# VehicleBattVMonIoT_SMD.net
KiCad netlist of a schematic drawn in EAGLE
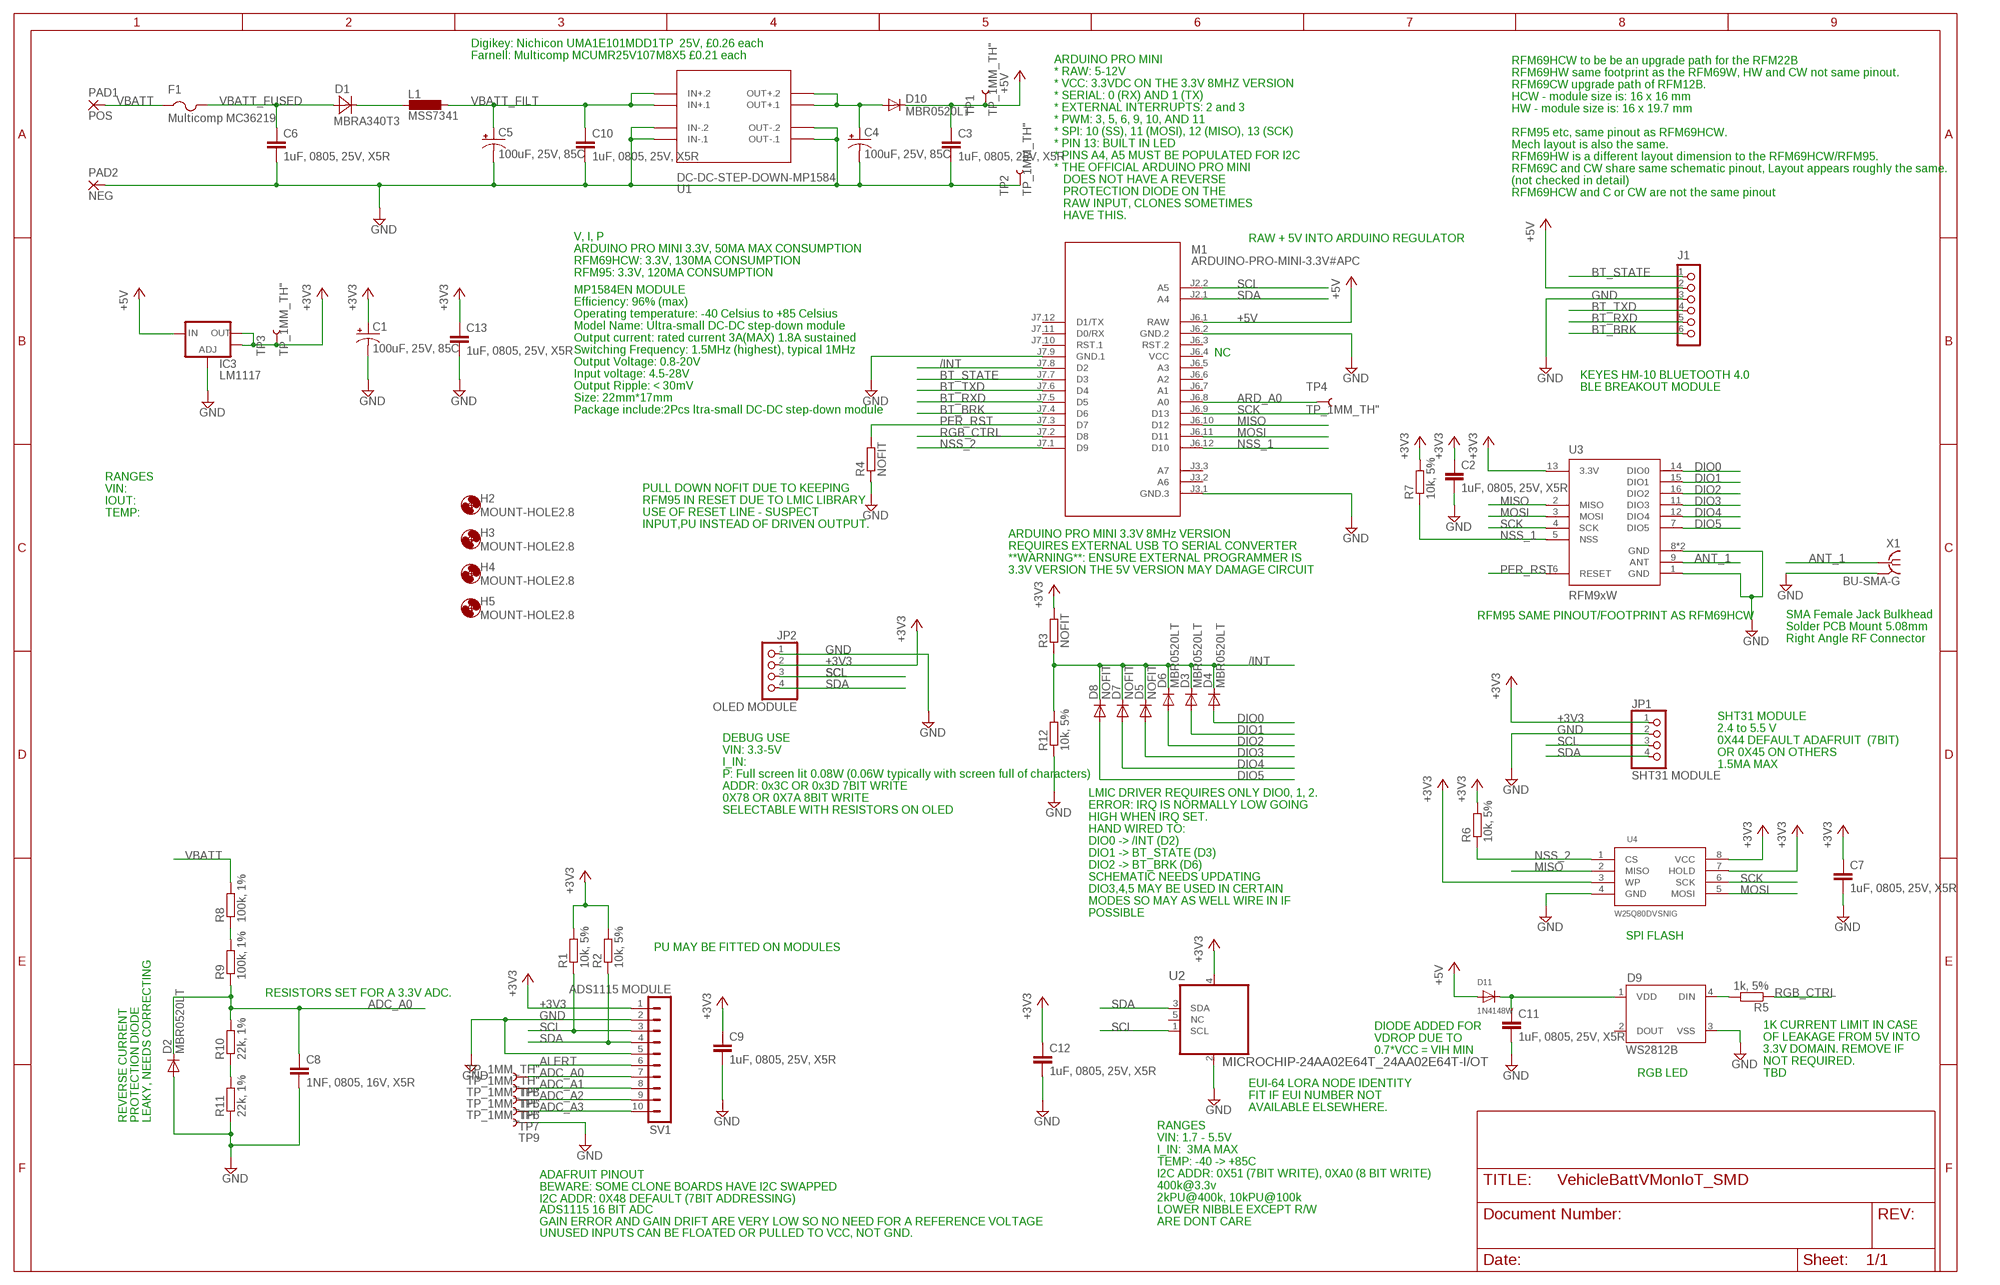
[diagram p0: schematic, sheet 1]

(export (version "E")
  (design (tool "Eeschema 10.0.6"))
  (components
    (comp (ref "C1")
      (value "100uF, 25V, 85C")
      (footprint "eagle-import:CPOL-RADIAL-100UF-25V")
      (fields (field (name "MF") "MULTICOMP") (field (name "MPN") "MCUMR25V107M8X5"))
      (libsource (lib "eagle-import") (part "CAP_POLPTH1"))
    )
    (comp (ref "C2")
      (value "1uF, 0805, 25V, X5R")
      (footprint "eagle-import:C0805")
      (fields (field (name "MF") "MULTICOMP") (field (name "MPN") "MC0805X105K250CT"))
      (libsource (lib "eagle-import") (part "C-EUC0805"))
    )
    (comp (ref "C3")
      (value "1uF, 0805, 25V, X5R")
      (footprint "eagle-import:C0805")
      (fields (field (name "MF") "MULTICOMP") (field (name "MPN") "MC0805X105K250CT"))
      (libsource (lib "eagle-import") (part "C-EUC0805"))
    )
    (comp (ref "C4")
      (value "100uF, 25V, 85C")
      (footprint "eagle-import:CPOL-RADIAL-100UF-25V")
      (fields (field (name "MF") "MULTICOMP") (field (name "MPN") "MCUMR25V107M8X5"))
      (libsource (lib "eagle-import") (part "CAP_POLPTH1"))
    )
    (comp (ref "C5")
      (value "100uF, 25V, 85C")
      (footprint "eagle-import:CPOL-RADIAL-100UF-25V")
      (fields (field (name "MF") "MULTICOMP") (field (name "MPN") "MCUMR25V107M8X5"))
      (libsource (lib "eagle-import") (part "CAP_POLPTH1"))
    )
    (comp (ref "C6")
      (value "1uF, 0805, 25V, X5R")
      (footprint "eagle-import:C0805")
      (fields (field (name "MF") "MULTICOMP") (field (name "MPN") "MC0805X105K250CT"))
      (libsource (lib "eagle-import") (part "C-EUC0805"))
    )
    (comp (ref "C7")
      (value "1uF, 0805, 25V, X5R")
      (footprint "eagle-import:C0805")
      (fields (field (name "MF") "MULTICOMP") (field (name "MPN") "MC0805X105K250CT"))
      (libsource (lib "eagle-import") (part "C-EUC0805"))
    )
    (comp (ref "C8")
      (value "1NF, 0805, 16V, X5R")
      (footprint "eagle-import:C0805")
      (fields (field (name "MF") "MULTICOMP") (field (name "MPN") "MCSH21B102K160CT"))
      (libsource (lib "eagle-import") (part "C-EUC0805"))
    )
    (comp (ref "C9")
      (value "1uF, 0805, 25V, X5R")
      (footprint "eagle-import:C0805")
      (fields (field (name "MF") "MULTICOMP") (field (name "MPN") "MC0805X105K250CT"))
      (libsource (lib "eagle-import") (part "C-EUC0805"))
    )
    (comp (ref "C10")
      (value "1uF, 0805, 25V, X5R")
      (footprint "eagle-import:C0805")
      (fields (field (name "MF") "MULTICOMP") (field (name "MPN") "MC0805X105K250CT"))
      (libsource (lib "eagle-import") (part "C-EUC0805"))
    )
    (comp (ref "C11")
      (value "1uF, 0805, 25V, X5R")
      (footprint "eagle-import:C0805")
      (fields (field (name "MF") "MULTICOMP") (field (name "MPN") "MC0805X105K250CT"))
      (libsource (lib "eagle-import") (part "C-EUC0805"))
    )
    (comp (ref "C12")
      (value "1uF, 0805, 25V, X5R")
      (footprint "eagle-import:C0805")
      (fields (field (name "MF") "MULTICOMP") (field (name "MPN") "MC0805X105K250CT"))
      (libsource (lib "eagle-import") (part "C-EUC0805"))
    )
    (comp (ref "C13")
      (value "1uF, 0805, 25V, X5R")
      (footprint "eagle-import:C0805")
      (fields (field (name "MF") "MULTICOMP") (field (name "MPN") "MC0805X105K250CT"))
      (libsource (lib "eagle-import") (part "C-EUC0805"))
    )
    (comp (ref "D1")
      (value "MBRA340T3")
      (footprint "eagle-import:SMA")
      (fields (field (name "MF") "ON SEMICONDUCTOR") (field (name "MPN") "MBRA340T3G"))
      (libsource (lib "eagle-import") (part "MBRA340T3"))
    )
    (comp (ref "D2")
      (value "MBR0520LT")
      (footprint "eagle-import:SOD123")
      (fields (field (name "MF") "DIODES INC.") (field (name "MPN") "B0520LW-7-F"))
      (libsource (lib "eagle-import") (part "MBR0520LT"))
    )
    (comp (ref "D3")
      (value "MBR0520LT")
      (footprint "eagle-import:SOD123")
      (fields (field (name "MF") "DIODES INC.") (field (name "MPN") "B0520LW-7-F"))
      (libsource (lib "eagle-import") (part "MBR0520LT"))
    )
    (comp (ref "D4")
      (value "MBR0520LT")
      (footprint "eagle-import:SOD123")
      (fields (field (name "MF") "DIODES INC.") (field (name "MPN") "B0520LW-7-F"))
      (libsource (lib "eagle-import") (part "MBR0520LT"))
    )
    (comp (ref "D5")
      (value "NOFIT")
      (footprint "eagle-import:SOD123")
      (fields (field (name "MF") "DIODES INC.") (field (name "MPN") "B0520LW-7-F"))
      (libsource (lib "eagle-import") (part "MBR0520LT"))
    )
    (comp (ref "D6")
      (value "MBR0520LT")
      (footprint "eagle-import:SOD123")
      (fields (field (name "MF") "DIODES INC.") (field (name "MPN") "B0520LW-7-F"))
      (libsource (lib "eagle-import") (part "MBR0520LT"))
    )
    (comp (ref "D7")
      (value "NOFIT")
      (footprint "eagle-import:SOD123")
      (fields (field (name "MF") "DIODES INC.") (field (name "MPN") "B0520LW-7-F"))
      (libsource (lib "eagle-import") (part "MBR0520LT"))
    )
    (comp (ref "D8")
      (value "NOFIT")
      (footprint "eagle-import:SOD123")
      (fields (field (name "MF") "DIODES INC.") (field (name "MPN") "B0520LW-7-F"))
      (libsource (lib "eagle-import") (part "MBR0520LT"))
    )
    (comp (ref "D9")
      (value "WS2812B")
      (footprint "eagle-import:WS2812B")
      (libsource (lib "eagle-import") (part "WS2812B"))
    )
    (comp (ref "D10")
      (value "MBR0520LT")
      (footprint "eagle-import:SOD123")
      (fields (field (name "MF") "DIODES INC.") (field (name "MPN") "B0520LW-7-F"))
      (libsource (lib "eagle-import") (part "MBR0520LT"))
    )
    (comp (ref "D11")
      (value "1N4148W")
      (footprint "eagle-import:SOD-323F")
      (fields (field (name "MF") "MULTICOMP") (field (name "MPN") "1N4148WS."))
      (libsource (lib "eagle-import") (part "DIODESOD-323F"))
    )
    (comp (ref "F1")
      (value "Multicomp MC36219")
      (footprint "eagle-import:1812")
      (fields (field (name "MF") "MULTICOMP") (field (name "MPN") "MC36219."))
      (libsource (lib "eagle-import") (part "PTCFUSE-1812"))
    )
    (comp (ref "H2")
      (value "MOUNT-HOLE2.8")
      (footprint "eagle-import:2,8")
      (libsource (lib "eagle-import") (part "MOUNT-HOLE2.8"))
    )
    (comp (ref "H3")
      (value "MOUNT-HOLE2.8")
      (footprint "eagle-import:2,8")
      (libsource (lib "eagle-import") (part "MOUNT-HOLE2.8"))
    )
    (comp (ref "H4")
      (value "MOUNT-HOLE2.8")
      (footprint "eagle-import:2,8")
      (libsource (lib "eagle-import") (part "MOUNT-HOLE2.8"))
    )
    (comp (ref "H5")
      (value "MOUNT-HOLE2.8")
      (footprint "eagle-import:2,8")
      (libsource (lib "eagle-import") (part "MOUNT-HOLE2.8"))
    )
    (comp (ref "IC3")
      (value "LM1117")
      (footprint "eagle-import:SOT223")
      (fields (field (name "MF") "STMICROELECTRONICS") (field (name "MPN") "LD1117S33TR"))
      (libsource (lib "eagle-import") (part "V_REG_LM1117SOT223"))
    )
    (comp (ref "J1")
      (value "HM-10 MODULE")
      (footprint "eagle-import:M1X6_MALE_RIGHT_ANGLED_SMD")
      (libsource (lib "eagle-import") (part "CON_HEADER_1X06-SMD-RIGHT-ANGLED"))
    )
    (comp (ref "JP1")
      (value "SHT31 MODULE")
      (footprint "eagle-import:1X04")
      (libsource (lib "eagle-import") (part "PINHD-1X4"))
    )
    (comp (ref "JP2")
      (value "OLED MODULE")
      (footprint "eagle-import:1X04")
      (libsource (lib "eagle-import") (part "PINHD-1X4"))
    )
    (comp (ref "L1")
      (value "MSS7341")
      (footprint "eagle-import:MSS7341")
      (fields (field (name "MF") "COILCRAFT") (field (name "MPN") "MSS7341-683MLD"))
      (libsource (lib "eagle-import") (part "MSS7341"))
    )
    (comp (ref "M1")
      (value "ARDUINO-PRO-MINI-3.3V#APC")
      (footprint "eagle-import:ARDUINO-PRO-MINI#APC")
      (libsource (lib "eagle-import") (part "ARDUINO-PRO-MINI-#APC3.3V"))
    )
    (comp (ref "PAD1")
      (value "POS")
      (footprint "eagle-import:3,81_1,4")
      (libsource (lib "eagle-import") (part "3,81/1,4"))
    )
    (comp (ref "PAD2")
      (value "NEG")
      (footprint "eagle-import:3,81_1,4")
      (libsource (lib "eagle-import") (part "3,81/1,4"))
    )
    (comp (ref "R1")
      (value "10k, 5%")
      (footprint "eagle-import:R0805")
      (fields (field (name "MF") "MULTICOMP") (field (name "MPN") "MC01W0805510K"))
      (libsource (lib "eagle-import") (part "R-EU_R0805"))
    )
    (comp (ref "R2")
      (value "10k, 5%")
      (footprint "eagle-import:R0805")
      (fields (field (name "MF") "MULTICOMP") (field (name "MPN") "MC01W0805510K"))
      (libsource (lib "eagle-import") (part "R-EU_R0805"))
    )
    (comp (ref "R3")
      (value "NOFIT")
      (footprint "eagle-import:R0805")
      (fields (field (name "MF") "MULTICOMP") (field (name "MPN") "MC01W0805510K"))
      (libsource (lib "eagle-import") (part "R-EU_R0805"))
    )
    (comp (ref "R4")
      (value "NOFIT")
      (footprint "eagle-import:R0805")
      (fields (field (name "MF") "MULTICOMP") (field (name "MPN") "MC01W0805510K"))
      (libsource (lib "eagle-import") (part "R-EU_R0805"))
    )
    (comp (ref "R5")
      (value "1k, 5%")
      (footprint "eagle-import:R0805")
      (fields (field (name "MF") "WELWYN") (field (name "MPN") "WCR0805-1K0FI"))
      (libsource (lib "eagle-import") (part "R-EU_R0805"))
    )
    (comp (ref "R6")
      (value "10k, 5%")
      (footprint "eagle-import:R0805")
      (fields (field (name "MF") "MULTICOMP") (field (name "MPN") "MC01W0805510K"))
      (libsource (lib "eagle-import") (part "R-EU_R0805"))
    )
    (comp (ref "R7")
      (value "10k, 5%")
      (footprint "eagle-import:R0805")
      (fields (field (name "MF") "MULTICOMP") (field (name "MPN") "MC01W0805510K"))
      (libsource (lib "eagle-import") (part "R-EU_R0805"))
    )
    (comp (ref "R8")
      (value "100k, 1%")
      (footprint "eagle-import:R0805")
      (fields (field (name "MF") "YAGEO (PHYCOMP)") (field (name "MPN") "RC0805FR-07100KL"))
      (libsource (lib "eagle-import") (part "R-EU_R0805"))
    )
    (comp (ref "R9")
      (value "100k, 1%")
      (footprint "eagle-import:R0805")
      (fields (field (name "MF") "YAGEO (PHYCOMP)") (field (name "MPN") "RC0805FR-07100KL"))
      (libsource (lib "eagle-import") (part "R-EU_R0805"))
    )
    (comp (ref "R10")
      (value "22k, 1%")
      (footprint "eagle-import:R0805")
      (fields (field (name "MF") "WELWYN") (field (name "MPN") "WCR0805-22KFI"))
      (libsource (lib "eagle-import") (part "R-EU_R0805"))
    )
    (comp (ref "R11")
      (value "22k, 1%")
      (footprint "eagle-import:R0805")
      (fields (field (name "MF") "WELWYN") (field (name "MPN") "WCR0805-22KFI"))
      (libsource (lib "eagle-import") (part "R-EU_R0805"))
    )
    (comp (ref "R12")
      (value "10k, 5%")
      (footprint "eagle-import:R0805")
      (fields (field (name "MF") "MULTICOMP") (field (name "MPN") "MC01W0805510K"))
      (libsource (lib "eagle-import") (part "R-EU_R0805"))
    )
    (comp (ref "SV1")
      (value "ADS1115 MODULE")
      (footprint "eagle-import:MA10-1W")
      (libsource (lib "eagle-import") (part "MA10-1W"))
    )
    (comp (ref "TP1")
      (value "TP_1MM_TH\"")
      (footprint "eagle-import:TP_1MM_TH")
      (libsource (lib "eagle-import") (part "TP_1MM_TH{dblquote}"))
    )
    (comp (ref "TP2")
      (value "TP_1MM_TH\"")
      (footprint "eagle-import:TP_1MM_TH")
      (libsource (lib "eagle-import") (part "TP_1MM_TH{dblquote}"))
    )
    (comp (ref "TP3")
      (value "TP_1MM_TH\"")
      (footprint "eagle-import:TP_1MM_TH")
      (libsource (lib "eagle-import") (part "TP_1MM_TH{dblquote}"))
    )
    (comp (ref "TP4")
      (value "TP_1MM_TH\"")
      (footprint "eagle-import:TP_1MM_TH")
      (libsource (lib "eagle-import") (part "TP_1MM_TH{dblquote}"))
    )
    (comp (ref "TP5")
      (value "TP_1MM_TH\"")
      (footprint "eagle-import:TP_1MM_TH")
      (libsource (lib "eagle-import") (part "TP_1MM_TH{dblquote}"))
    )
    (comp (ref "TP6")
      (value "TP_1MM_TH\"")
      (footprint "eagle-import:TP_1MM_TH")
      (libsource (lib "eagle-import") (part "TP_1MM_TH{dblquote}"))
    )
    (comp (ref "TP7")
      (value "TP_1MM_TH\"")
      (footprint "eagle-import:TP_1MM_TH")
      (libsource (lib "eagle-import") (part "TP_1MM_TH{dblquote}"))
    )
    (comp (ref "TP8")
      (value "TP_1MM_TH\"")
      (footprint "eagle-import:TP_1MM_TH")
      (libsource (lib "eagle-import") (part "TP_1MM_TH{dblquote}"))
    )
    (comp (ref "TP9")
      (value "TP_1MM_TH\"")
      (footprint "eagle-import:TP_1MM_TH")
      (libsource (lib "eagle-import") (part "TP_1MM_TH{dblquote}"))
    )
    (comp (ref "U1")
      (value "DC-DC-STEP-DOWN-MP1584")
      (footprint "eagle-import:DC-DC-STEP-DOWN-MP1584")
      (libsource (lib "eagle-import") (part "DC-DC-STEP-DOWN-MP1584"))
    )
    (comp (ref "U2")
      (value "MICROCHIP-24AA02E64T_24AA02E64T-I/OT")
      (footprint "eagle-import:MICROCHIP-24AA02E64T_SOT95P270X145-5N")
      (fields (field (name "MPN") "24AA02E64T-I/OT"))
      (libsource (lib "eagle-import") (part "MICROCHIP-24AA02E64T_24AA02E64T-I/OT"))
    )
    (comp (ref "U3")
      (value "RFM9xW")
      (footprint "eagle-import:RFM69HCW-XXXS2")
      (libsource (lib "eagle-import") (part "RFM69HCW"))
    )
    (comp (ref "U4")
      (value "W25Q80DVSNIG")
      (footprint "eagle-import:SO08")
      (libsource (lib "eagle-import") (part "SPI_FLASH-X25XXSMD"))
    )
    (comp (ref "X1")
      (value "BU-SMA-G")
      (footprint "eagle-import:BU-SMA-G")
      (fields
        (field (name "MF") "AMP - TE CONNECTIVITY")
        (field (name "MPN") "5-1814400-1")
        (field (name "OC_FARNELL") "1248989")
      )
      (libsource (lib "eagle-import") (part "BU-SMA-G"))
    )
  )
  (nets
    (net (code "1") (name "+3V3") (class "Default")
      (node (ref "C1") (pin "1") (pinfunction "+_1") (pintype "passive"))
      (node (ref "C12") (pin "1") (pinfunction "1_1") (pintype "passive"))
      (node (ref "C13") (pin "1") (pinfunction "1_1") (pintype "passive"))
      (node (ref "C2") (pin "1") (pinfunction "1_1") (pintype "passive"))
      (node (ref "C7") (pin "1") (pinfunction "1_1") (pintype "passive"))
      (node (ref "C9") (pin "1") (pinfunction "1_1") (pintype "passive"))
      (node (ref "IC3") (pin "2") (pinfunction "OUT_2") (pintype "output"))
      (node (ref "IC3") (pin "4") (pinfunction "OUT_4") (pintype "output"))
      (node (ref "JP1") (pin "1") (pinfunction "1_1") (pintype "passive"))
      (node (ref "JP2") (pin "2") (pinfunction "2_2") (pintype "passive"))
      (node (ref "R1") (pin "2") (pinfunction "2_2") (pintype "passive"))
      (node (ref "R2") (pin "2") (pinfunction "2_2") (pintype "passive"))
      (node (ref "R3") (pin "2") (pinfunction "2_2") (pintype "passive"))
      (node (ref "R6") (pin "2") (pinfunction "2_2") (pintype "passive"))
      (node (ref "R7") (pin "2") (pinfunction "2_2") (pintype "passive"))
      (node (ref "SV1") (pin "1") (pinfunction "1_1") (pintype "passive"))
      (node (ref "TP3") (pin "P$1") (pinfunction "1_P$1") (pintype "bidirectional"))
      (node (ref "U2") (pin "4") (pinfunction "VCC_4") (pintype "power_in"))
      (node (ref "U3") (pin "13") (pinfunction "3.3V_13") (pintype "power_in"))
      (node (ref "U4") (pin "3") (pinfunction "WP_3") (pintype "bidirectional"))
      (node (ref "U4") (pin "7") (pinfunction "HOLD_7") (pintype "bidirectional"))
      (node (ref "U4") (pin "8") (pinfunction "VCC_8") (pintype "bidirectional"))
    )
    (net (code "2") (name "+5V") (class "Default")
      (node (ref "C3") (pin "1") (pinfunction "1_1") (pintype "passive"))
      (node (ref "D10") (pin "C") (pinfunction "C_C") (pintype "passive"))
      (node (ref "D11") (pin "A") (pinfunction "A_A") (pintype "passive"))
      (node (ref "IC3") (pin "3") (pinfunction "IN_3") (pintype "input"))
      (node (ref "J1") (pin "2") (pinfunction "2_2") (pintype "bidirectional"))
      (node (ref "M1") (pin "J6.1") (pinfunction "RAW_J6.1") (pintype "power_in"))
      (node (ref "TP1") (pin "P$1") (pinfunction "1_P$1") (pintype "bidirectional"))
    )
    (net (code "3") (name "/ADC_A0") (class "Default")
      (node (ref "C8") (pin "1") (pinfunction "1_1") (pintype "passive"))
      (node (ref "D2") (pin "C") (pinfunction "C_C") (pintype "passive"))
      (node (ref "R10") (pin "2") (pinfunction "2_2") (pintype "passive"))
      (node (ref "R9") (pin "1") (pinfunction "1_1") (pintype "passive"))
      (node (ref "SV1") (pin "7") (pinfunction "7_7") (pintype "passive"))
      (node (ref "TP8") (pin "P$1") (pinfunction "1_P$1") (pintype "bidirectional"))
    )
    (net (code "4") (name "/ADC_A1") (class "Default")
      (node (ref "SV1") (pin "8") (pinfunction "8_8") (pintype "passive"))
      (node (ref "TP5") (pin "P$1") (pinfunction "1_P$1") (pintype "bidirectional"))
    )
    (net (code "5") (name "/ADC_A2") (class "Default")
      (node (ref "SV1") (pin "9") (pinfunction "9_9") (pintype "passive"))
      (node (ref "TP6") (pin "P$1") (pinfunction "1_P$1") (pintype "bidirectional"))
    )
    (net (code "6") (name "/ADC_A3") (class "Default")
      (node (ref "SV1") (pin "10") (pinfunction "10_10") (pintype "passive"))
      (node (ref "TP7") (pin "P$1") (pinfunction "1_P$1") (pintype "bidirectional"))
    )
    (net (code "7") (name "/ALERT") (class "Default")
      (node (ref "SV1") (pin "6") (pinfunction "6_6") (pintype "passive"))
    )
    (net (code "8") (name "/ANT_1") (class "Default")
      (node (ref "U3") (pin "9") (pinfunction "ANT_9") (pintype "passive"))
      (node (ref "X1") (pin "1") (pinfunction "1_1") (pintype "passive"))
    )
    (net (code "9") (name "/ARD_A0") (class "Default")
      (node (ref "M1") (pin "J6.8") (pinfunction "A0_J6.8") (pintype "bidirectional"))
      (node (ref "TP4") (pin "P$1") (pinfunction "1_P$1") (pintype "bidirectional"))
    )
    (net (code "10") (name "/BT_BRK") (class "Default")
      (node (ref "J1") (pin "6") (pinfunction "6_6") (pintype "passive"))
      (node (ref "M1") (pin "J7.4") (pinfunction "D6_J7.4") (pintype "bidirectional"))
    )
    (net (code "11") (name "/BT_RXD") (class "Default")
      (node (ref "J1") (pin "5") (pinfunction "5_5") (pintype "passive"))
      (node (ref "M1") (pin "J7.5") (pinfunction "D5_J7.5") (pintype "bidirectional"))
    )
    (net (code "12") (name "/BT_STATE") (class "Default")
      (node (ref "J1") (pin "1") (pinfunction "1_1") (pintype "bidirectional"))
      (node (ref "M1") (pin "J7.7") (pinfunction "D3_J7.7") (pintype "bidirectional"))
    )
    (net (code "13") (name "/BT_TXD") (class "Default")
      (node (ref "J1") (pin "4") (pinfunction "4_4") (pintype "passive"))
      (node (ref "M1") (pin "J7.6") (pinfunction "D4_J7.6") (pintype "bidirectional"))
    )
    (net (code "14") (name "/DIO0") (class "Default")
      (node (ref "D4") (pin "A") (pinfunction "A_A") (pintype "passive"))
      (node (ref "U3") (pin "14") (pinfunction "DIO0_14") (pintype "bidirectional"))
    )
    (net (code "15") (name "/DIO1") (class "Default")
      (node (ref "D3") (pin "A") (pinfunction "A_A") (pintype "passive"))
      (node (ref "U3") (pin "15") (pinfunction "DIO1_15") (pintype "bidirectional"))
    )
    (net (code "16") (name "/DIO2") (class "Default")
      (node (ref "D6") (pin "A") (pinfunction "A_A") (pintype "passive"))
      (node (ref "U3") (pin "16") (pinfunction "DIO2_16") (pintype "bidirectional"))
    )
    (net (code "17") (name "/DIO3") (class "Default")
      (node (ref "D5") (pin "A") (pinfunction "A_A") (pintype "passive"))
      (node (ref "U3") (pin "11") (pinfunction "DIO3_11") (pintype "bidirectional"))
    )
    (net (code "18") (name "/DIO4") (class "Default")
      (node (ref "D7") (pin "A") (pinfunction "A_A") (pintype "passive"))
      (node (ref "U3") (pin "12") (pinfunction "DIO4_12") (pintype "bidirectional"))
    )
    (net (code "19") (name "/DIO5") (class "Default")
      (node (ref "D8") (pin "A") (pinfunction "A_A") (pintype "passive"))
      (node (ref "U3") (pin "7") (pinfunction "DIO5_7") (pintype "bidirectional"))
    )
    (net (code "20") (name "/MISO") (class "Default")
      (node (ref "M1") (pin "J6.10") (pinfunction "D12_J6.10") (pintype "bidirectional"))
      (node (ref "U3") (pin "2") (pinfunction "MISO_2") (pintype "bidirectional"))
      (node (ref "U4") (pin "2") (pinfunction "MISO_2") (pintype "bidirectional"))
    )
    (net (code "21") (name "/MOSI") (class "Default")
      (node (ref "M1") (pin "J6.11") (pinfunction "D11_J6.11") (pintype "bidirectional"))
      (node (ref "U3") (pin "3") (pinfunction "MOSI_3") (pintype "input"))
      (node (ref "U4") (pin "5") (pinfunction "MOSI_5") (pintype "bidirectional"))
    )
    (net (code "22") (name "/NSS_1") (class "Default")
      (node (ref "M1") (pin "J6.12") (pinfunction "D10_J6.12") (pintype "bidirectional"))
      (node (ref "R7") (pin "1") (pinfunction "1_1") (pintype "passive"))
      (node (ref "U3") (pin "5") (pinfunction "NSS_5") (pintype "input"))
    )
    (net (code "23") (name "/NSS_2") (class "Default")
      (node (ref "M1") (pin "J7.1") (pinfunction "D9_J7.1") (pintype "bidirectional"))
      (node (ref "R6") (pin "1") (pinfunction "1_1") (pintype "passive"))
      (node (ref "U4") (pin "1") (pinfunction "CS_1") (pintype "bidirectional"))
    )
    (net (code "24") (name "/PER_RST") (class "Default")
      (node (ref "M1") (pin "J7.3") (pinfunction "D7_J7.3") (pintype "bidirectional"))
      (node (ref "R4") (pin "2") (pinfunction "2_2") (pintype "passive"))
      (node (ref "U3") (pin "6") (pinfunction "RESET_6") (pintype "input"))
    )
    (net (code "25") (name "/RGB_CTRL") (class "Default")
      (node (ref "M1") (pin "J7.2") (pinfunction "D8_J7.2") (pintype "bidirectional"))
      (node (ref "R5") (pin "1") (pinfunction "1_1") (pintype "passive"))
    )
    (net (code "26") (name "/SCK") (class "Default")
      (node (ref "M1") (pin "J6.9") (pinfunction "D13_J6.9") (pintype "bidirectional"))
      (node (ref "U3") (pin "4") (pinfunction "SCK_4") (pintype "input"))
      (node (ref "U4") (pin "6") (pinfunction "SCK_6") (pintype "bidirectional"))
    )
    (net (code "27") (name "/SCL") (class "Default")
      (node (ref "JP1") (pin "3") (pinfunction "3_3") (pintype "passive"))
      (node (ref "JP2") (pin "3") (pinfunction "3_3") (pintype "passive"))
      (node (ref "M1") (pin "J2.2") (pinfunction "A5_J2.2") (pintype "bidirectional"))
      (node (ref "R1") (pin "1") (pinfunction "1_1") (pintype "passive"))
      (node (ref "SV1") (pin "3") (pinfunction "3_3") (pintype "passive"))
      (node (ref "U2") (pin "1") (pinfunction "SCL_1") (pintype "input"))
    )
    (net (code "28") (name "/SDA") (class "Default")
      (node (ref "JP1") (pin "4") (pinfunction "4_4") (pintype "passive"))
      (node (ref "JP2") (pin "4") (pinfunction "4_4") (pintype "passive"))
      (node (ref "M1") (pin "J2.1") (pinfunction "A4_J2.1") (pintype "bidirectional"))
      (node (ref "R2") (pin "1") (pinfunction "1_1") (pintype "passive"))
      (node (ref "SV1") (pin "4") (pinfunction "4_4") (pintype "passive"))
      (node (ref "U2") (pin "3") (pinfunction "SDA_3") (pintype "bidirectional"))
    )
    (net (code "29") (name "/VBATT") (class "Default")
      (node (ref "F1") (pin "1") (pinfunction "1_1") (pintype "passive"))
      (node (ref "PAD1") (pin "1") (pinfunction "P_1") (pintype "passive"))
      (node (ref "R8") (pin "2") (pinfunction "2_2") (pintype "passive"))
    )
    (net (code "30") (name "/VBATT_FILT") (class "Default")
      (node (ref "C10") (pin "1") (pinfunction "1_1") (pintype "passive"))
      (node (ref "C5") (pin "1") (pinfunction "+_1") (pintype "passive"))
      (node (ref "L1") (pin "2") (pinfunction "2_2") (pintype "passive"))
      (node (ref "U1") (pin "IN+.1") (pinfunction "IN+.1_IN+.1") (pintype "bidirectional"))
      (node (ref "U1") (pin "IN+.2") (pinfunction "IN+.2_IN+.2") (pintype "bidirectional"))
    )
    (net (code "31") (name "/VBATT_FUSED") (class "Default")
      (node (ref "C6") (pin "1") (pinfunction "1_1") (pintype "passive"))
      (node (ref "D1") (pin "A") (pinfunction "A_A") (pintype "passive"))
      (node (ref "F1") (pin "2") (pinfunction "2_2") (pintype "passive"))
    )
    (net (code "32") (name "/VCC") (class "Default")
      (node (ref "M1") (pin "J6.4") (pinfunction "VCC_J6.4") (pintype "power_in"))
    )
    (net (code "33") (name "/{slash}INT") (class "Default")
      (node (ref "D3") (pin "C") (pinfunction "C_C") (pintype "passive"))
      (node (ref "D4") (pin "C") (pinfunction "C_C") (pintype "passive"))
      (node (ref "D5") (pin "C") (pinfunction "C_C") (pintype "passive"))
      (node (ref "D6") (pin "C") (pinfunction "C_C") (pintype "passive"))
      (node (ref "D7") (pin "C") (pinfunction "C_C") (pintype "passive"))
      (node (ref "D8") (pin "C") (pinfunction "C_C") (pintype "passive"))
      (node (ref "M1") (pin "J7.8") (pinfunction "D2_J7.8") (pintype "bidirectional"))
      (node (ref "R12") (pin "2") (pinfunction "2_2") (pintype "passive"))
      (node (ref "R3") (pin "1") (pinfunction "1_1") (pintype "passive"))
    )
    (net (code "34") (name "GND") (class "Default")
      (node (ref "C1") (pin "2") (pinfunction "-_2") (pintype "passive"))
      (node (ref "C10") (pin "2") (pinfunction "2_2") (pintype "passive"))
      (node (ref "C11") (pin "2") (pinfunction "2_2") (pintype "passive"))
      (node (ref "C12") (pin "2") (pinfunction "2_2") (pintype "passive"))
      (node (ref "C13") (pin "2") (pinfunction "2_2") (pintype "passive"))
      (node (ref "C2") (pin "2") (pinfunction "2_2") (pintype "passive"))
      (node (ref "C3") (pin "2") (pinfunction "2_2") (pintype "passive"))
      (node (ref "C4") (pin "2") (pinfunction "-_2") (pintype "passive"))
      (node (ref "C5") (pin "2") (pinfunction "-_2") (pintype "passive"))
      (node (ref "C6") (pin "2") (pinfunction "2_2") (pintype "passive"))
      (node (ref "C7") (pin "2") (pinfunction "2_2") (pintype "passive"))
      (node (ref "C8") (pin "2") (pinfunction "2_2") (pintype "passive"))
      (node (ref "C9") (pin "2") (pinfunction "2_2") (pintype "passive"))
      (node (ref "D2") (pin "A") (pinfunction "A_A") (pintype "passive"))
      (node (ref "D9") (pin "3") (pinfunction "VSS_3") (pintype "power_in"))
      (node (ref "IC3") (pin "1") (pinfunction "ADJ_1") (pintype "input"))
      (node (ref "J1") (pin "3") (pinfunction "3_3") (pintype "passive"))
      (node (ref "JP1") (pin "2") (pinfunction "2_2") (pintype "passive"))
      (node (ref "JP2") (pin "1") (pinfunction "1_1") (pintype "passive"))
      (node (ref "M1") (pin "J3.1") (pinfunction "GND.3_J3.1") (pintype "bidirectional"))
      (node (ref "M1") (pin "J6.2") (pinfunction "GND.2_J6.2") (pintype "power_in"))
      (node (ref "M1") (pin "J7.9") (pinfunction "GND.1_J7.9") (pintype "power_in"))
      (node (ref "PAD2") (pin "1") (pinfunction "P_1") (pintype "passive"))
      (node (ref "R11") (pin "1") (pinfunction "1_1") (pintype "passive"))
      (node (ref "R12") (pin "1") (pinfunction "1_1") (pintype "passive"))
      (node (ref "R4") (pin "1") (pinfunction "1_1") (pintype "passive"))
      (node (ref "SV1") (pin "2") (pinfunction "2_2") (pintype "passive"))
      (node (ref "SV1") (pin "5") (pinfunction "5_5") (pintype "passive"))
      (node (ref "TP2") (pin "P$1") (pinfunction "1_P$1") (pintype "bidirectional"))
      (node (ref "TP9") (pin "P$1") (pinfunction "1_P$1") (pintype "bidirectional"))
      (node (ref "U1") (pin "IN-.1") (pinfunction "IN-.1_IN-.1") (pintype "bidirectional"))
      (node (ref "U1") (pin "IN-.2") (pinfunction "IN-.2_IN-.2") (pintype "bidirectional"))
      (node (ref "U1") (pin "OUT-.1") (pinfunction "OUT-.1_OUT-.1") (pintype "bidirectional"))
      (node (ref "U1") (pin "OUT-.2") (pinfunction "OUT-.2_OUT-.2") (pintype "bidirectional"))
      (node (ref "U2") (pin "2") (pinfunction "VSS_2") (pintype "power_in"))
      (node (ref "U3") (pin "1") (pinfunction "GND_1") (pintype "power_in"))
      (node (ref "U3") (pin "10") (pinfunction "GND_10") (pintype "power_in"))
      (node (ref "U3") (pin "8") (pinfunction "GND_8") (pintype "power_in"))
      (node (ref "U4") (pin "4") (pinfunction "GND_4") (pintype "bidirectional"))
      (node (ref "X1") (pin "2") (pinfunction "2_2") (pintype "passive"))
      (node (ref "X1") (pin "3") (pinfunction "2_3") (pintype "passive"))
      (node (ref "X1") (pin "4") (pinfunction "2_4") (pintype "passive"))
      (node (ref "X1") (pin "5") (pinfunction "2_5") (pintype "passive"))
    )
    (net (code "35") (name "Net-(C4-+)") (class "Default")
      (node (ref "C4") (pin "1") (pinfunction "+_1") (pintype "passive"))
      (node (ref "D10") (pin "A") (pinfunction "A_A") (pintype "passive"))
      (node (ref "U1") (pin "OUT+.1") (pinfunction "OUT+.1_OUT+.1") (pintype "bidirectional"))
      (node (ref "U1") (pin "OUT+.2") (pinfunction "OUT+.2_OUT+.2") (pintype "bidirectional"))
    )
    (net (code "36") (name "Net-(D1-PadC)") (class "Default")
      (node (ref "D1") (pin "C") (pinfunction "C_C") (pintype "passive"))
      (node (ref "L1") (pin "1") (pinfunction "1_1") (pintype "passive"))
    )
    (net (code "37") (name "Net-(D9-DIN)") (class "Default")
      (node (ref "D9") (pin "4") (pinfunction "DIN_4") (pintype "input"))
      (node (ref "R5") (pin "2") (pinfunction "2_2") (pintype "passive"))
    )
    (net (code "38") (name "Net-(D9-VDD)") (class "Default")
      (node (ref "C11") (pin "1") (pinfunction "1_1") (pintype "passive"))
      (node (ref "D11") (pin "C") (pinfunction "C_C") (pintype "passive"))
      (node (ref "D9") (pin "1") (pinfunction "VDD_1") (pintype "power_in"))
    )
    (net (code "39") (name "Net-(R8-Pad1)") (class "Default")
      (node (ref "R8") (pin "1") (pinfunction "1_1") (pintype "passive"))
      (node (ref "R9") (pin "2") (pinfunction "2_2") (pintype "passive"))
    )
    (net (code "40") (name "Net-(R10-Pad1)") (class "Default")
      (node (ref "R10") (pin "1") (pinfunction "1_1") (pintype "passive"))
      (node (ref "R11") (pin "2") (pinfunction "2_2") (pintype "passive"))
    )
    (net (code "41") (name "unconnected-(D9-DOUT-Pad2)") (class "Default")
      (node (ref "D9") (pin "2") (pinfunction "DOUT_2") (pintype "output"))
    )
    (net (code "42") (name "unconnected-(M1-A1-PadJ6.7)") (class "Default")
      (node (ref "M1") (pin "J6.7") (pinfunction "A1_J6.7") (pintype "bidirectional"))
    )
    (net (code "43") (name "unconnected-(M1-A2-PadJ6.6)") (class "Default")
      (node (ref "M1") (pin "J6.6") (pinfunction "A2_J6.6") (pintype "bidirectional"))
    )
    (net (code "44") (name "unconnected-(M1-A3-PadJ6.5)") (class "Default")
      (node (ref "M1") (pin "J6.5") (pinfunction "A3_J6.5") (pintype "bidirectional"))
    )
    (net (code "45") (name "unconnected-(M1-A6-PadJ3.2)") (class "Default")
      (node (ref "M1") (pin "J3.2") (pinfunction "A6_J3.2") (pintype "bidirectional"))
    )
    (net (code "46") (name "unconnected-(M1-A7-PadJ3.3)") (class "Default")
      (node (ref "M1") (pin "J3.3") (pinfunction "A7_J3.3") (pintype "bidirectional"))
    )
    (net (code "47") (name "unconnected-(M1-D0{slash}RX-PadJ7.11)") (class "Default")
      (node (ref "M1") (pin "J7.11") (pinfunction "D0/RX_J7.11") (pintype "bidirectional"))
    )
    (net (code "48") (name "unconnected-(M1-D1{slash}TX-PadJ7.12)") (class "Default")
      (node (ref "M1") (pin "J7.12") (pinfunction "D1/TX_J7.12") (pintype "bidirectional"))
    )
    (net (code "49") (name "unconnected-(M1-RST.1-PadJ7.10)") (class "Default")
      (node (ref "M1") (pin "J7.10") (pinfunction "RST.1_J7.10") (pintype "bidirectional"))
    )
    (net (code "50") (name "unconnected-(M1-RST.2-PadJ6.3)") (class "Default")
      (node (ref "M1") (pin "J6.3") (pinfunction "RST.2_J6.3") (pintype "bidirectional"))
    )
    (net (code "51") (name "unconnected-(U2-NC-Pad5)") (class "Default")
      (node (ref "U2") (pin "5") (pinfunction "NC_5") (pintype "no_connect"))
    )
  )
)
